# PikaCharge_V2.net
KiCad netlist of a schematic drawn in EAGLE
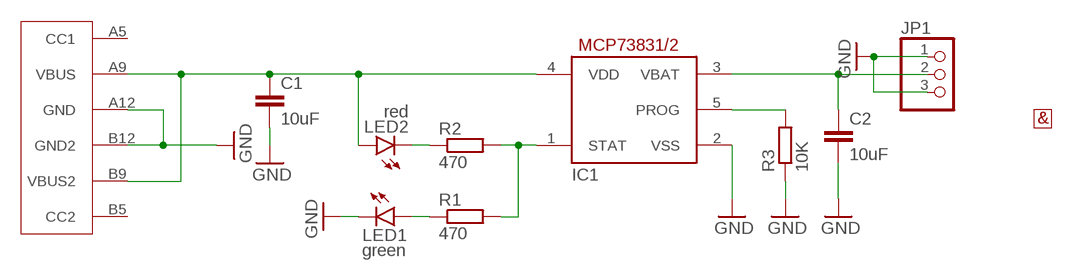
[diagram p0: schematic, sheet 1]

(export (version "E")
  (design (tool "Eeschema 10.0.6"))
  (components
    (comp (ref "C1")
      (value "10uF")
      (footprint "eagle-import:C0805")
      (libsource (lib "eagle-import") (part "C-EUC0805"))
    )
    (comp (ref "C2")
      (value "10uF")
      (footprint "eagle-import:C0805")
      (libsource (lib "eagle-import") (part "C-EUC0805"))
    )
    (comp (ref "IC1")
      (value "MCP73831/OT")
      (footprint "eagle-import:SOT23-5L")
      (libsource (lib "eagle-import") (part "MCP73831/OT"))
    )
    (comp (ref "JP1")
      (value "PINHD-1X03_2.54-S")
      (footprint "eagle-import:1X03-S")
      (libsource (lib "eagle-import") (part "PINHD-1X03_2.54-S"))
    )
    (comp (ref "LED1")
      (value "green")
      (footprint "eagle-import:CHIP-LED0805")
      (libsource (lib "eagle-import") (part "LEDCHIP-LED0805"))
    )
    (comp (ref "LED2")
      (value "red")
      (footprint "eagle-import:CHIP-LED0805")
      (libsource (lib "eagle-import") (part "LEDCHIP-LED0805"))
    )
    (comp (ref "R1")
      (value "470")
      (footprint "eagle-import:R0805")
      (libsource (lib "eagle-import") (part "R-EU_R0805"))
    )
    (comp (ref "R2")
      (value "470")
      (footprint "eagle-import:R0805")
      (libsource (lib "eagle-import") (part "R-EU_R0805"))
    )
    (comp (ref "R3")
      (value "10K")
      (footprint "eagle-import:R0805")
      (libsource (lib "eagle-import") (part "R-EU_R0805"))
    )
    (comp (ref "U$1")
      (value "USB-C-6PIN")
      (footprint "eagle-import:USB-C-6PIN")
      (libsource (lib "eagle-import") (part "USB-C-6PIN"))
    )
    (comp (ref "U$2")
      (value "AMP-HALF")
      (footprint "eagle-import:AMP-HALF")
      (libsource (lib "eagle-import") (part "AMP-HALF"))
    )
  )
  (nets
    (net (code "1") (name "GND") (class "Default")
      (node (ref "C1") (pin "2") (pinfunction "2_2") (pintype "passive"))
      (node (ref "C2") (pin "2") (pinfunction "2_2") (pintype "passive"))
      (node (ref "IC1") (pin "2") (pinfunction "VSS_2") (pintype "power_in"))
      (node (ref "JP1") (pin "1") (pinfunction "1_1") (pintype "passive"))
      (node (ref "JP1") (pin "3") (pinfunction "3_3") (pintype "passive"))
      (node (ref "LED1") (pin "C") (pinfunction "C_C") (pintype "passive"))
      (node (ref "R3") (pin "1") (pinfunction "1_1") (pintype "passive"))
      (node (ref "U$1") (pin "A12") (pinfunction "GND_A12") (pintype "bidirectional"))
      (node (ref "U$1") (pin "B12") (pinfunction "GND2_B12") (pintype "bidirectional"))
    )
    (net (code "2") (name "Net-(IC1-PROG)") (class "Default")
      (node (ref "IC1") (pin "5") (pinfunction "PROG_5") (pintype "input"))
      (node (ref "R3") (pin "2") (pinfunction "2_2") (pintype "passive"))
    )
    (net (code "3") (name "Net-(IC1-STAT)") (class "Default")
      (node (ref "IC1") (pin "1") (pinfunction "STAT_1") (pintype "output"))
      (node (ref "R1") (pin "2") (pinfunction "2_2") (pintype "passive"))
      (node (ref "R2") (pin "2") (pinfunction "2_2") (pintype "passive"))
    )
    (net (code "4") (name "Net-(IC1-VBAT)") (class "Default")
      (node (ref "C2") (pin "1") (pinfunction "1_1") (pintype "passive"))
      (node (ref "IC1") (pin "3") (pinfunction "VBAT_3") (pintype "bidirectional"))
      (node (ref "JP1") (pin "2") (pinfunction "2_2") (pintype "passive"))
    )
    (net (code "5") (name "Net-(IC1-VDD)") (class "Default")
      (node (ref "C1") (pin "1") (pinfunction "1_1") (pintype "passive"))
      (node (ref "IC1") (pin "4") (pinfunction "VDD_4") (pintype "power_in"))
      (node (ref "LED2") (pin "A") (pinfunction "A_A") (pintype "passive"))
      (node (ref "U$1") (pin "A9") (pinfunction "VBUS_A9") (pintype "bidirectional"))
      (node (ref "U$1") (pin "B9") (pinfunction "VBUS2_B9") (pintype "bidirectional"))
    )
    (net (code "6") (name "Net-(LED1-PadA)") (class "Default")
      (node (ref "LED1") (pin "A") (pinfunction "A_A") (pintype "passive"))
      (node (ref "R1") (pin "1") (pinfunction "1_1") (pintype "passive"))
    )
    (net (code "7") (name "Net-(LED2-PadC)") (class "Default")
      (node (ref "LED2") (pin "C") (pinfunction "C_C") (pintype "passive"))
      (node (ref "R2") (pin "1") (pinfunction "1_1") (pintype "passive"))
    )
    (net (code "8") (name "unconnected-(U$1-CC1-PadA5)") (class "Default")
      (node (ref "U$1") (pin "A5") (pinfunction "CC1_A5") (pintype "bidirectional"))
    )
    (net (code "9") (name "unconnected-(U$1-CC2-PadB5)") (class "Default")
      (node (ref "U$1") (pin "B5") (pinfunction "CC2_B5") (pintype "bidirectional"))
    )
  )
)
